# DCDCConverterUP.net
KiCad netlist of a schematic drawn in Altium Designer
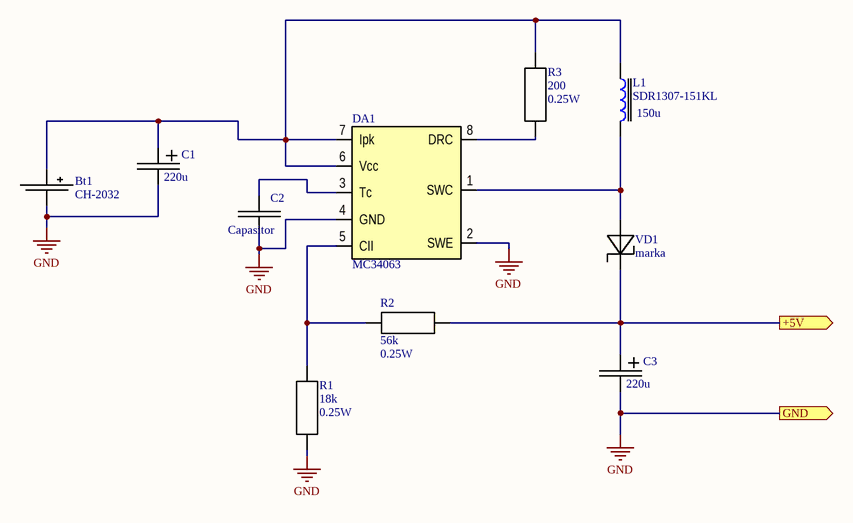
[diagram p0: DCDCConverterUP.SchDoc]

(export (version "E")
  (design (tool "Eeschema 10.0.6"))
  (components
    (comp (ref "Bt1")
      (value "CH-2032")
      (footprint "CH25-2032")
      (fields (field (name "PART NUMBER") "CH25-2032") (field (name "MANUFACTURER") "Comf"))
      (libsource (lib "SchlibUGO") (part "CR-2032"))
    )
    (comp (ref "C1")
      (value "220u")
      (footprint "Type D")
      (fields
        (field (name "PART NUMBER") "T520D227M010ATE018")
        (field (name "MANUFACTURER") "Kemet")
        (field (name "POWER") "10V")
      )
      (libsource (lib "SchlibUGO") (part "Capasitor Electrolit"))
    )
    (comp (ref "C2")
      (value "Capasitor")
      (footprint "CAP1206")
      (fields
        (field (name "VOLTAGE") "50V")
        (field (name "PART NUMBER") "1206471X7R50V")
        (field (name "MANUFACTURER") "FAITHFULL LINK")
      )
      (libsource (lib "SchlibUGO") (part "Capasitor"))
    )
    (comp (ref "C3")
      (value "220u")
      (footprint "Type D")
      (fields
        (field (name "PART NUMBER") "T520D227M010ATE018")
        (field (name "MANUFACTURER") "Kemet")
        (field (name "POWER") "10V")
      )
      (libsource (lib "SchlibUGO") (part "Capasitor Electrolit"))
    )
    (comp (ref "DA1")
      (value "MC34063")
      (footprint "SO-8")
      (fields (field (name "PART NUMBER") "MC34063AG") (field (name "MANUFACTURER") "UTC"))
      (libsource (lib "SchlibUGO") (part "MC34063"))
    )
    (comp (ref "L1")
      (value "SDR1307-151KL")
      (footprint "SDR1307-151KL")
      (fields (field (name "ALTIUM_VALUE") "150u") (field (name "MANUFACTURER") "BOURNS"))
      (libsource (lib "SchlibUGO") (part "SDR1307-151KL"))
    )
    (comp (ref "R1")
      (value "18k")
      (footprint "1206")
      (fields
        (field (name "MANUFACTURER") "China")
        (field (name "PART NUMBER") "1206183")
        (field (name "POWER") "0.25W")
        (field (name "Comment") "Resistor")
      )
      (libsource (lib "SchlibUGO") (part "Resistor"))
    )
    (comp (ref "R2")
      (value "56k")
      (footprint "1206")
      (fields
        (field (name "MANUFACTURER") "china")
        (field (name "PART NUMBER") "1206563")
        (field (name "POWER") "0.25W")
        (field (name "Comment") "Resistor")
      )
      (libsource (lib "SchlibUGO") (part "Resistor"))
    )
    (comp (ref "R3")
      (value "200")
      (footprint "1206")
      (fields
        (field (name "MANUFACTURER") "China")
        (field (name "PART NUMBER") "SMD12065221")
        (field (name "POWER") "0.25W")
        (field (name "Comment") "Resistor")
      )
      (libsource (lib "SchlibUGO") (part "Resistor"))
    )
    (comp (ref "VD1")
      (value "marka")
      (footprint "SOD-23")
      (fields (field (name "PART NUMBER") "1N5819HW") (field (name "POWER") "40V"))
      (libsource (lib "SchlibUGO") (part "DiodeShottki"))
    )
  )
  (nets
    (net (code "1") (name "/+5V") (class "Default")
      (node (ref "C3") (pin "1") (pinfunction "1_1") (pintype "passive"))
      (node (ref "R2") (pin "1") (pinfunction "1_1") (pintype "passive"))
      (node (ref "VD1") (pin "2") (pinfunction "2_2") (pintype "passive"))
    )
    (net (code "2") (name "GND") (class "Default")
      (node (ref "Bt1") (pin "2") (pinfunction "2_2") (pintype "passive"))
      (node (ref "C1") (pin "2") (pinfunction "2_2") (pintype "passive"))
      (node (ref "C2") (pin "2") (pinfunction "2_2") (pintype "passive"))
      (node (ref "C3") (pin "2") (pinfunction "2_2") (pintype "passive"))
      (node (ref "DA1") (pin "2") (pinfunction "SWE_2") (pintype "passive"))
      (node (ref "DA1") (pin "4") (pinfunction "GND_4") (pintype "passive"))
      (node (ref "R1") (pin "1") (pinfunction "1_1") (pintype "passive"))
    )
    (net (code "3") (name "Net-(DA1-CII)") (class "Default")
      (node (ref "DA1") (pin "5") (pinfunction "CII_5") (pintype "passive"))
      (node (ref "R1") (pin "2") (pinfunction "2_2") (pintype "passive"))
      (node (ref "R2") (pin "2") (pinfunction "2_2") (pintype "passive"))
    )
    (net (code "4") (name "Net-(DA1-DRC)") (class "Default")
      (node (ref "DA1") (pin "8") (pinfunction "DRC_8") (pintype "passive"))
      (node (ref "R3") (pin "1") (pinfunction "1_1") (pintype "passive"))
    )
    (net (code "5") (name "Net-(DA1-Ipk)") (class "Default")
      (node (ref "Bt1") (pin "1") (pinfunction "1_1") (pintype "passive"))
      (node (ref "C1") (pin "1") (pinfunction "1_1") (pintype "passive"))
      (node (ref "DA1") (pin "6") (pinfunction "Vcc_6") (pintype "passive"))
      (node (ref "DA1") (pin "7") (pinfunction "Ipk_7") (pintype "passive"))
      (node (ref "L1") (pin "2") (pinfunction "2_2") (pintype "passive"))
      (node (ref "R3") (pin "2") (pinfunction "2_2") (pintype "passive"))
    )
    (net (code "6") (name "Net-(DA1-SWC)") (class "Default")
      (node (ref "DA1") (pin "1") (pinfunction "SWC_1") (pintype "passive"))
      (node (ref "L1") (pin "1") (pinfunction "1_1") (pintype "passive"))
      (node (ref "VD1") (pin "1") (pinfunction "1_1") (pintype "passive"))
    )
    (net (code "7") (name "Net-(DA1-Tc)") (class "Default")
      (node (ref "C2") (pin "1") (pinfunction "1_1") (pintype "passive"))
      (node (ref "DA1") (pin "3") (pinfunction "Tc_3") (pintype "passive"))
    )
  )
)
